# RATT_REV1.net
KiCad netlist of a schematic drawn in EAGLE
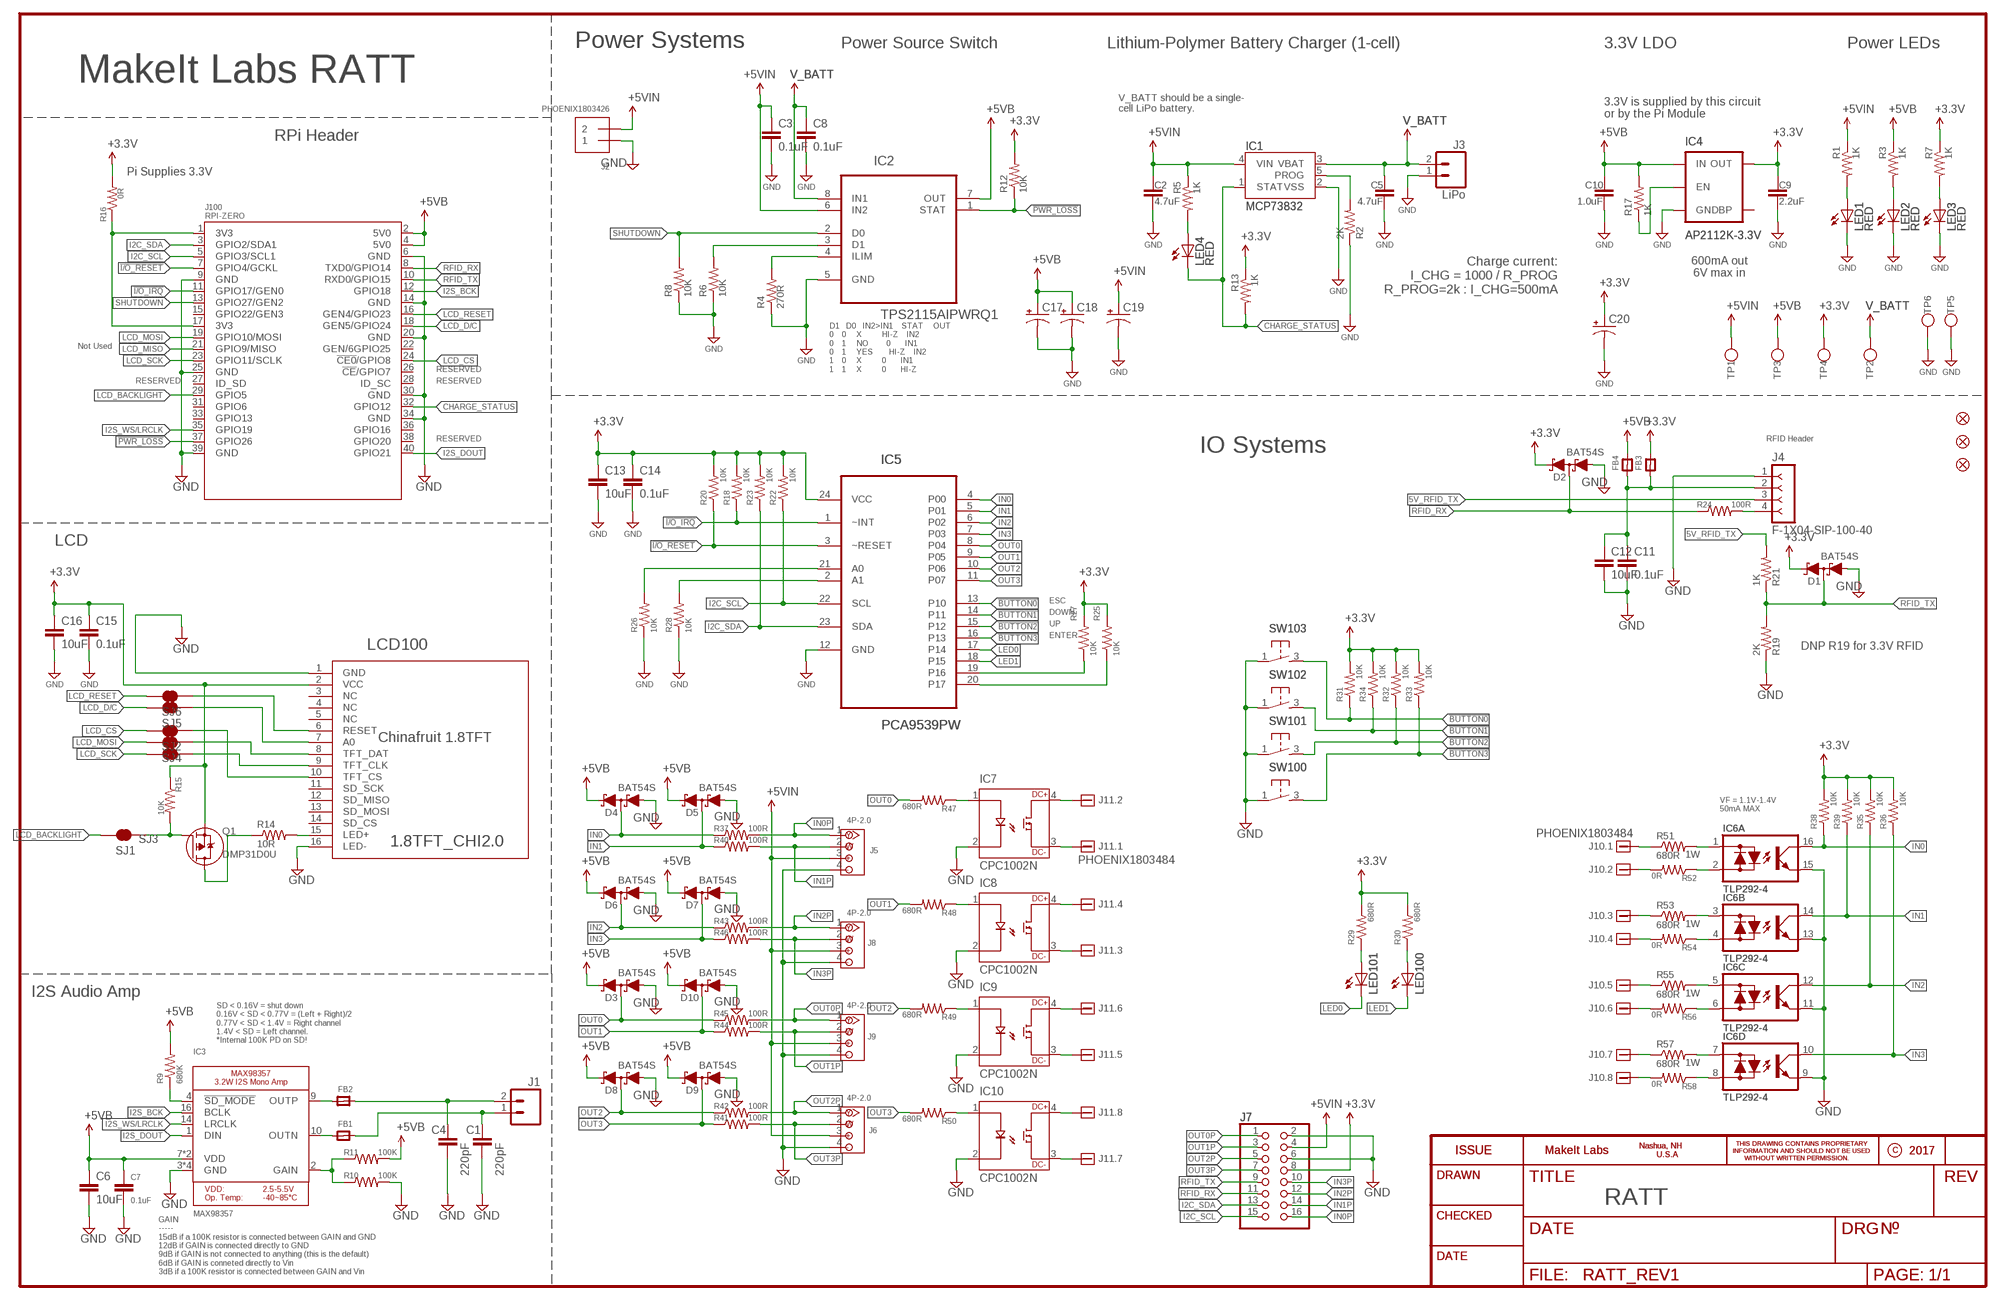
[diagram p0: schematic, sheet 1]

(export (version "E")
  (design (tool "Eeschema 10.0.6"))
  (components
    (comp (ref "C1")
      (value "220pF")
      (footprint "eagle-import:0603-CAP")
      (libsource (lib "eagle-import") (part "CAP0603"))
    )
    (comp (ref "C2")
      (value "4.7uF")
      (footprint "eagle-import:0603-CAP")
      (libsource (lib "eagle-import") (part "CAP0603"))
    )
    (comp (ref "C3")
      (value "0.1uF")
      (footprint "eagle-import:0603-CAP")
      (libsource (lib "eagle-import") (part "CAP0603"))
    )
    (comp (ref "C4")
      (value "220pF")
      (footprint "eagle-import:0603-CAP")
      (libsource (lib "eagle-import") (part "CAP0603"))
    )
    (comp (ref "C5")
      (value "4.7uF")
      (footprint "eagle-import:0603-CAP")
      (libsource (lib "eagle-import") (part "CAP0603"))
    )
    (comp (ref "C6")
      (value "10uF")
      (footprint "eagle-import:0805-CAP")
      (libsource (lib "eagle-import") (part "CAP0805"))
    )
    (comp (ref "C7")
      (value "0.1uF")
      (footprint "eagle-import:0603-CAP")
      (libsource (lib "eagle-import") (part "CAP0603"))
    )
    (comp (ref "C8")
      (value "0.1uF")
      (footprint "eagle-import:0603-CAP")
      (libsource (lib "eagle-import") (part "CAP0603"))
    )
    (comp (ref "C9")
      (value "2.2uF")
      (footprint "eagle-import:0603-CAP")
      (libsource (lib "eagle-import") (part "CAP0603"))
    )
    (comp (ref "C10")
      (value "1.0uF")
      (footprint "eagle-import:0603-CAP")
      (libsource (lib "eagle-import") (part "CAP0603"))
    )
    (comp (ref "C11")
      (value "0.1uF")
      (footprint "eagle-import:0603-CAP")
      (libsource (lib "eagle-import") (part "CAP0603"))
    )
    (comp (ref "C12")
      (value "10uF")
      (footprint "eagle-import:0805-CAP")
      (libsource (lib "eagle-import") (part "CAP0805"))
    )
    (comp (ref "C13")
      (value "10uF")
      (footprint "eagle-import:0805-CAP")
      (libsource (lib "eagle-import") (part "CAP0805"))
    )
    (comp (ref "C14")
      (value "0.1uF")
      (footprint "eagle-import:0603-CAP")
      (libsource (lib "eagle-import") (part "CAP0603"))
    )
    (comp (ref "C15")
      (value "0.1uF")
      (footprint "eagle-import:0603-CAP")
      (libsource (lib "eagle-import") (part "CAP0603"))
    )
    (comp (ref "C16")
      (value "10uF")
      (footprint "eagle-import:0805-CAP")
      (libsource (lib "eagle-import") (part "CAP0805"))
    )
    (comp (ref "C17")
      (value "CPOL-USD")
      (footprint "eagle-import:PANASONIC_D")
      (libsource (lib "eagle-import") (part "CPOL-USD"))
    )
    (comp (ref "C18")
      (value "CPOL-USD")
      (footprint "eagle-import:PANASONIC_D")
      (libsource (lib "eagle-import") (part "CPOL-USD"))
    )
    (comp (ref "C19")
      (value "CPOL-USD")
      (footprint "eagle-import:PANASONIC_D")
      (libsource (lib "eagle-import") (part "CPOL-USD"))
    )
    (comp (ref "C20")
      (value "CPOL-USD")
      (footprint "eagle-import:PANASONIC_D")
      (libsource (lib "eagle-import") (part "CPOL-USD"))
    )
    (comp (ref "D1")
      (value "BAT54S")
      (footprint "eagle-import:SOT-23")
      (libsource (lib "eagle-import") (part "BAT54S"))
    )
    (comp (ref "D2")
      (value "BAT54S")
      (footprint "eagle-import:SOT-23")
      (libsource (lib "eagle-import") (part "BAT54S"))
    )
    (comp (ref "D3")
      (value "BAT54S")
      (footprint "eagle-import:SOT-23")
      (libsource (lib "eagle-import") (part "BAT54S"))
    )
    (comp (ref "D4")
      (value "BAT54S")
      (footprint "eagle-import:SOT-23")
      (libsource (lib "eagle-import") (part "BAT54S"))
    )
    (comp (ref "D5")
      (value "BAT54S")
      (footprint "eagle-import:SOT-23")
      (libsource (lib "eagle-import") (part "BAT54S"))
    )
    (comp (ref "D6")
      (value "BAT54S")
      (footprint "eagle-import:SOT-23")
      (libsource (lib "eagle-import") (part "BAT54S"))
    )
    (comp (ref "D7")
      (value "BAT54S")
      (footprint "eagle-import:SOT-23")
      (libsource (lib "eagle-import") (part "BAT54S"))
    )
    (comp (ref "D8")
      (value "BAT54S")
      (footprint "eagle-import:SOT-23")
      (libsource (lib "eagle-import") (part "BAT54S"))
    )
    (comp (ref "D9")
      (value "BAT54S")
      (footprint "eagle-import:SOT-23")
      (libsource (lib "eagle-import") (part "BAT54S"))
    )
    (comp (ref "D10")
      (value "BAT54S")
      (footprint "eagle-import:SOT-23")
      (libsource (lib "eagle-import") (part "BAT54S"))
    )
    (comp (ref "FB1")
      (value "FERRITE")
      (footprint "eagle-import:0603")
      (libsource (lib "eagle-import") (part "FERRITE"))
    )
    (comp (ref "FB2")
      (value "FERRITE")
      (footprint "eagle-import:0603")
      (libsource (lib "eagle-import") (part "FERRITE"))
    )
    (comp (ref "FB3")
      (value "FERRITE")
      (footprint "eagle-import:0603")
      (libsource (lib "eagle-import") (part "FERRITE"))
    )
    (comp (ref "FB4")
      (value "FERRITE")
      (footprint "eagle-import:0603")
      (libsource (lib "eagle-import") (part "FERRITE"))
    )
    (comp (ref "FID1")
      (value "FIDUCIAL40MILX80MIL")
      (footprint "eagle-import:FIDUCIAL-40MILX80MIL")
      (libsource (lib "eagle-import") (part "FIDUCIAL40MILX80MIL"))
    )
    (comp (ref "FID2")
      (value "FIDUCIAL40MILX80MIL")
      (footprint "eagle-import:FIDUCIAL-40MILX80MIL")
      (libsource (lib "eagle-import") (part "FIDUCIAL40MILX80MIL"))
    )
    (comp (ref "FID3")
      (value "FIDUCIAL40MILX80MIL")
      (footprint "eagle-import:FIDUCIAL-40MILX80MIL")
      (libsource (lib "eagle-import") (part "FIDUCIAL40MILX80MIL"))
    )
    (comp (ref "IC1")
      (value "MCP73832")
      (footprint "eagle-import:SOT23-5")
      (libsource (lib "eagle-import") (part "MCP73831"))
    )
    (comp (ref "IC2")
      (value "TPS2115AIPWRQ1")
      (footprint "eagle-import:SOP65P640X120-8N")
      (libsource (lib "eagle-import") (part "TPS2115AIPWRQ1"))
    )
    (comp (ref "IC3")
      (value "MAX98357")
      (footprint "eagle-import:QFN16_3MM")
      (libsource (lib "eagle-import") (part "AUDIOAMP_MAX98357"))
    )
    (comp (ref "IC4")
      (value "AP2112K-3.3V")
      (footprint "eagle-import:SOT23-5")
      (libsource (lib "eagle-import") (part "V_REG_LDOSMD"))
    )
    (comp (ref "IC5")
      (value "PCA9539PW")
      (footprint "eagle-import:SOP65P640X120-24N")
      (libsource (lib "eagle-import") (part "PCA9539PW"))
    )
    (comp (ref "IC6")
      (value "TLP292-4")
      (footprint "eagle-import:SO-16")
      (libsource (lib "eagle-import") (part "TLP292-4"))
    )
    (comp (ref "IC7")
      (value "CPC1002N")
      (footprint "eagle-import:CPC1002N")
      (libsource (lib "eagle-import") (part "CPC1002N"))
    )
    (comp (ref "IC8")
      (value "CPC1002N")
      (footprint "eagle-import:CPC1002N")
      (libsource (lib "eagle-import") (part "CPC1002N"))
    )
    (comp (ref "IC9")
      (value "CPC1002N")
      (footprint "eagle-import:CPC1002N")
      (libsource (lib "eagle-import") (part "CPC1002N"))
    )
    (comp (ref "IC10")
      (value "CPC1002N")
      (footprint "eagle-import:CPC1002N")
      (libsource (lib "eagle-import") (part "CPC1002N"))
    )
    (comp (ref "J1")
      (value "M02POLAR")
      (footprint "eagle-import:MOLEX-1X2")
      (libsource (lib "eagle-import") (part "M02POLAR"))
    )
    (comp (ref "J2")
      (value "PHOENIX1803426")
      (footprint "eagle-import:1803426")
      (libsource (lib "eagle-import") (part "PHOENIX1803426"))
    )
    (comp (ref "J3")
      (value "LiPo")
      (footprint "eagle-import:JST-2-PTH")
      (libsource (lib "eagle-import") (part "M02JST-PTH-2"))
    )
    (comp (ref "J4")
      (value "F-1X04-SIP-100-40")
      (footprint "eagle-import:SIP-100-04-40")
      (libsource (lib "eagle-import") (part "F-1X04-SIP-100-40"))
    )
    (comp (ref "J5")
      (value "4P-2.0")
      (footprint "eagle-import:HW4-2.0")
      (libsource (lib "eagle-import") (part "GROVE-CONNECTOR-TH-VERT"))
    )
    (comp (ref "J6")
      (value "4P-2.0")
      (footprint "eagle-import:HW4-2.0")
      (libsource (lib "eagle-import") (part "GROVE-CONNECTOR-TH-VERT"))
    )
    (comp (ref "J7")
      (value "PINHD-2X8SHROUD")
      (footprint "eagle-import:2X08_SHROUD")
      (libsource (lib "eagle-import") (part "PINHD-2X8SHROUD"))
    )
    (comp (ref "J8")
      (value "4P-2.0")
      (footprint "eagle-import:HW4-2.0")
      (libsource (lib "eagle-import") (part "GROVE-CONNECTOR-TH-VERT"))
    )
    (comp (ref "J9")
      (value "4P-2.0")
      (footprint "eagle-import:HW4-2.0")
      (libsource (lib "eagle-import") (part "GROVE-CONNECTOR-TH-VERT"))
    )
    (comp (ref "J10")
      (value "PHOENIX1803484")
      (footprint "eagle-import:1803484")
      (libsource (lib "eagle-import") (part "PHOENIX1803484"))
    )
    (comp (ref "J11")
      (value "PHOENIX1803484")
      (footprint "eagle-import:1803484")
      (libsource (lib "eagle-import") (part "PHOENIX1803484"))
    )
    (comp (ref "J100")
      (value "RPI-ZERO")
      (footprint "eagle-import:RASPBERRYPI_BASTELSTUBE_V13_RASPI_BOARD_B+_FULL")
      (libsource (lib "eagle-import") (part "RPI-ZERO"))
    )
    (comp (ref "LCD100")
      (value "1.8TFT_CHI2.0")
      (footprint "eagle-import:1.8TFT_CHI_2.0")
      (libsource (lib "eagle-import") (part "1.8TFT_CHI2.0"))
    )
    (comp (ref "LED1")
      (value "RED")
      (footprint "eagle-import:LED-0603")
      (libsource (lib "eagle-import") (part "LED-RED0603"))
    )
    (comp (ref "LED2")
      (value "RED")
      (footprint "eagle-import:LED-0603")
      (libsource (lib "eagle-import") (part "LED-RED0603"))
    )
    (comp (ref "LED3")
      (value "RED")
      (footprint "eagle-import:LED-0603")
      (libsource (lib "eagle-import") (part "LED-RED0603"))
    )
    (comp (ref "LED4")
      (value "RED")
      (footprint "eagle-import:LED-0603")
      (libsource (lib "eagle-import") (part "LED-RED0603"))
    )
    (comp (ref "LED100")
      (value "LED5MM")
      (footprint "eagle-import:LED5MM")
      (libsource (lib "eagle-import") (part "LED5MM"))
    )
    (comp (ref "LED101")
      (value "LED5MM")
      (footprint "eagle-import:LED5MM")
      (libsource (lib "eagle-import") (part "LED5MM"))
    )
    (comp (ref "Q1")
      (value "DMP31D0U")
      (footprint "eagle-import:SOT23")
      (libsource (lib "eagle-import") (part "DMP31D0U"))
    )
    (comp (ref "R1")
      (value "1K")
      (footprint "eagle-import:0603-RES")
      (libsource (lib "eagle-import") (part "RESISTOR0603"))
    )
    (comp (ref "R2")
      (value "2K")
      (footprint "eagle-import:0603-RES")
      (libsource (lib "eagle-import") (part "RESISTOR0603"))
    )
    (comp (ref "R3")
      (value "1K")
      (footprint "eagle-import:0603-RES")
      (libsource (lib "eagle-import") (part "RESISTOR0603"))
    )
    (comp (ref "R4")
      (value "270R")
      (footprint "eagle-import:0603-RES")
      (libsource (lib "eagle-import") (part "RESISTOR0603"))
    )
    (comp (ref "R5")
      (value "1K")
      (footprint "eagle-import:0603-RES")
      (libsource (lib "eagle-import") (part "RESISTOR0603"))
    )
    (comp (ref "R6")
      (value "10K")
      (footprint "eagle-import:0603-RES")
      (libsource (lib "eagle-import") (part "RESISTOR0603"))
    )
    (comp (ref "R7")
      (value "1K")
      (footprint "eagle-import:0603-RES")
      (libsource (lib "eagle-import") (part "RESISTOR0603"))
    )
    (comp (ref "R8")
      (value "10K")
      (footprint "eagle-import:0603-RES")
      (libsource (lib "eagle-import") (part "RESISTOR0603"))
    )
    (comp (ref "R9")
      (value "680K")
      (footprint "eagle-import:0603-RES")
      (libsource (lib "eagle-import") (part "RESISTOR0603"))
    )
    (comp (ref "R10")
      (value "100K")
      (footprint "eagle-import:0603-RES")
      (libsource (lib "eagle-import") (part "RESISTOR0603"))
    )
    (comp (ref "R11")
      (value "100K")
      (footprint "eagle-import:0603-RES")
      (libsource (lib "eagle-import") (part "RESISTOR0603"))
    )
    (comp (ref "R12")
      (value "10K")
      (footprint "eagle-import:0603-RES")
      (libsource (lib "eagle-import") (part "RESISTOR0603"))
    )
    (comp (ref "R13")
      (value "1K")
      (footprint "eagle-import:0603-RES")
      (libsource (lib "eagle-import") (part "RESISTOR0603"))
    )
    (comp (ref "R14")
      (value "10R")
      (footprint "eagle-import:1206-RES")
      (libsource (lib "eagle-import") (part "RESISTOR1206"))
    )
    (comp (ref "R15")
      (value "10K")
      (footprint "eagle-import:0603-RES")
      (libsource (lib "eagle-import") (part "RESISTOR0603"))
    )
    (comp (ref "R16")
      (value "0R")
      (footprint "eagle-import:0603-RES")
      (libsource (lib "eagle-import") (part "RESISTOR0603"))
    )
    (comp (ref "R17")
      (value "1K")
      (footprint "eagle-import:0603-RES")
      (libsource (lib "eagle-import") (part "RESISTOR0603"))
    )
    (comp (ref "R18")
      (value "10K")
      (footprint "eagle-import:0603-RES")
      (libsource (lib "eagle-import") (part "RESISTOR0603"))
    )
    (comp (ref "R19")
      (value "2K")
      (footprint "eagle-import:0603-RES")
      (libsource (lib "eagle-import") (part "RESISTOR0603"))
    )
    (comp (ref "R20")
      (value "10K")
      (footprint "eagle-import:0603-RES")
      (libsource (lib "eagle-import") (part "RESISTOR0603"))
    )
    (comp (ref "R21")
      (value "1K")
      (footprint "eagle-import:0603-RES")
      (libsource (lib "eagle-import") (part "RESISTOR0603"))
    )
    (comp (ref "R22")
      (value "10K")
      (footprint "eagle-import:0603-RES")
      (libsource (lib "eagle-import") (part "RESISTOR0603"))
    )
    (comp (ref "R23")
      (value "10K")
      (footprint "eagle-import:0603-RES")
      (libsource (lib "eagle-import") (part "RESISTOR0603"))
    )
    (comp (ref "R24")
      (value "100R")
      (footprint "eagle-import:0603-RES")
      (libsource (lib "eagle-import") (part "RESISTOR0603"))
    )
    (comp (ref "R25")
      (value "10K")
      (footprint "eagle-import:0603-RES")
      (libsource (lib "eagle-import") (part "RESISTOR0603"))
    )
    (comp (ref "R26")
      (value "10K")
      (footprint "eagle-import:0603-RES")
      (libsource (lib "eagle-import") (part "RESISTOR0603"))
    )
    (comp (ref "R27")
      (value "10K")
      (footprint "eagle-import:0603-RES")
      (libsource (lib "eagle-import") (part "RESISTOR0603"))
    )
    (comp (ref "R28")
      (value "10K")
      (footprint "eagle-import:0603-RES")
      (libsource (lib "eagle-import") (part "RESISTOR0603"))
    )
    (comp (ref "R29")
      (value "680R")
      (footprint "eagle-import:0603-RES")
      (libsource (lib "eagle-import") (part "RESISTOR0603"))
    )
    (comp (ref "R30")
      (value "680R")
      (footprint "eagle-import:0603-RES")
      (libsource (lib "eagle-import") (part "RESISTOR0603"))
    )
    (comp (ref "R31")
      (value "10K")
      (footprint "eagle-import:0603-RES")
      (libsource (lib "eagle-import") (part "RESISTOR0603"))
    )
    (comp (ref "R32")
      (value "10K")
      (footprint "eagle-import:0603-RES")
      (libsource (lib "eagle-import") (part "RESISTOR0603"))
    )
    (comp (ref "R33")
      (value "10K")
      (footprint "eagle-import:0603-RES")
      (libsource (lib "eagle-import") (part "RESISTOR0603"))
    )
    (comp (ref "R34")
      (value "10K")
      (footprint "eagle-import:0603-RES")
      (libsource (lib "eagle-import") (part "RESISTOR0603"))
    )
    (comp (ref "R35")
      (value "10K")
      (footprint "eagle-import:0603-RES")
      (libsource (lib "eagle-import") (part "RESISTOR0603"))
    )
    (comp (ref "R36")
      (value "10K")
      (footprint "eagle-import:0603-RES")
      (libsource (lib "eagle-import") (part "RESISTOR0603"))
    )
    (comp (ref "R37")
      (value "100R")
      (footprint "eagle-import:0603-RES")
      (libsource (lib "eagle-import") (part "RESISTOR0603"))
    )
    (comp (ref "R38")
      (value "10K")
      (footprint "eagle-import:0603-RES")
      (libsource (lib "eagle-import") (part "RESISTOR0603"))
    )
    (comp (ref "R39")
      (value "10K")
      (footprint "eagle-import:0603-RES")
      (libsource (lib "eagle-import") (part "RESISTOR0603"))
    )
    (comp (ref "R40")
      (value "100R")
      (footprint "eagle-import:0603-RES")
      (libsource (lib "eagle-import") (part "RESISTOR0603"))
    )
    (comp (ref "R41")
      (value "100R")
      (footprint "eagle-import:0603-RES")
      (libsource (lib "eagle-import") (part "RESISTOR0603"))
    )
    (comp (ref "R42")
      (value "100R")
      (footprint "eagle-import:0603-RES")
      (libsource (lib "eagle-import") (part "RESISTOR0603"))
    )
    (comp (ref "R43")
      (value "100R")
      (footprint "eagle-import:0603-RES")
      (libsource (lib "eagle-import") (part "RESISTOR0603"))
    )
    (comp (ref "R44")
      (value "100R")
      (footprint "eagle-import:0603-RES")
      (libsource (lib "eagle-import") (part "RESISTOR0603"))
    )
    (comp (ref "R45")
      (value "100R")
      (footprint "eagle-import:0603-RES")
      (libsource (lib "eagle-import") (part "RESISTOR0603"))
    )
    (comp (ref "R46")
      (value "100R")
      (footprint "eagle-import:0603-RES")
      (libsource (lib "eagle-import") (part "RESISTOR0603"))
    )
    (comp (ref "R47")
      (value "680R")
      (footprint "eagle-import:0603-RES")
      (libsource (lib "eagle-import") (part "RESISTOR0603"))
    )
    (comp (ref "R48")
      (value "680R")
      (footprint "eagle-import:0603-RES")
      (libsource (lib "eagle-import") (part "RESISTOR0603"))
    )
    (comp (ref "R49")
      (value "680R")
      (footprint "eagle-import:0603-RES")
      (libsource (lib "eagle-import") (part "RESISTOR0603"))
    )
    (comp (ref "R50")
      (value "680R")
      (footprint "eagle-import:0603-RES")
      (libsource (lib "eagle-import") (part "RESISTOR0603"))
    )
    (comp (ref "R51")
      (value "680R")
      (footprint "eagle-import:2512-RES")
      (fields (field (name "P") "1W"))
      (libsource (lib "eagle-import") (part "RESISTOR2512"))
    )
    (comp (ref "R52")
      (value "0R")
      (footprint "eagle-import:0603-RES")
      (libsource (lib "eagle-import") (part "RESISTOR0603"))
    )
    (comp (ref "R53")
      (value "680R")
      (footprint "eagle-import:2512-RES")
      (fields (field (name "P") "1W"))
      (libsource (lib "eagle-import") (part "RESISTOR2512"))
    )
    (comp (ref "R54")
      (value "0R")
      (footprint "eagle-import:0603-RES")
      (libsource (lib "eagle-import") (part "RESISTOR0603"))
    )
    (comp (ref "R55")
      (value "680R")
      (footprint "eagle-import:2512-RES")
      (fields (field (name "P") "1W"))
      (libsource (lib "eagle-import") (part "RESISTOR2512"))
    )
    (comp (ref "R56")
      (value "0R")
      (footprint "eagle-import:0603-RES")
      (libsource (lib "eagle-import") (part "RESISTOR0603"))
    )
    (comp (ref "R57")
      (value "680R")
      (footprint "eagle-import:2512-RES")
      (fields (field (name "P") "1W"))
      (libsource (lib "eagle-import") (part "RESISTOR2512"))
    )
    (comp (ref "R58")
      (value "0R")
      (footprint "eagle-import:0603-RES")
      (libsource (lib "eagle-import") (part "RESISTOR0603"))
    )
    (comp (ref "SJ1")
      (value "JUMPER-PAD-2-NC_BY_TRACE")
      (footprint "eagle-import:SOLDERJUMPER_10MIL")
      (libsource (lib "eagle-import") (part "SOLDERJUMPER_CLOSED10MIL"))
    )
    (comp (ref "SJ2")
      (value "JUMPER-PAD-2-NC_BY_TRACE")
      (footprint "eagle-import:SOLDERJUMPER_10MIL")
      (libsource (lib "eagle-import") (part "SOLDERJUMPER_CLOSED10MIL"))
    )
    (comp (ref "SJ3")
      (value "JUMPER-PAD-2-NC_BY_TRACE")
      (footprint "eagle-import:SOLDERJUMPER_10MIL")
      (libsource (lib "eagle-import") (part "SOLDERJUMPER_CLOSED10MIL"))
    )
    (comp (ref "SJ4")
      (value "JUMPER-PAD-2-NC_BY_TRACE")
      (footprint "eagle-import:SOLDERJUMPER_10MIL")
      (libsource (lib "eagle-import") (part "SOLDERJUMPER_CLOSED10MIL"))
    )
    (comp (ref "SJ5")
      (value "JUMPER-PAD-2-NC_BY_TRACE")
      (footprint "eagle-import:SOLDERJUMPER_10MIL")
      (libsource (lib "eagle-import") (part "SOLDERJUMPER_CLOSED10MIL"))
    )
    (comp (ref "SJ6")
      (value "JUMPER-PAD-2-NC_BY_TRACE")
      (footprint "eagle-import:SOLDERJUMPER_10MIL")
      (libsource (lib "eagle-import") (part "SOLDERJUMPER_CLOSED10MIL"))
    )
    (comp (ref "SW100")
      (value "ESWITCH_320")
      (footprint "eagle-import:ESWITCH320")
      (libsource (lib "eagle-import") (part "ESWITCH_320"))
    )
    (comp (ref "SW101")
      (value "ESWITCH_320")
      (footprint "eagle-import:ESWITCH320")
      (libsource (lib "eagle-import") (part "ESWITCH_320"))
    )
    (comp (ref "SW102")
      (value "ESWITCH_320")
      (footprint "eagle-import:ESWITCH320")
      (libsource (lib "eagle-import") (part "ESWITCH_320"))
    )
    (comp (ref "SW103")
      (value "ESWITCH_320")
      (footprint "eagle-import:ESWITCH320")
      (libsource (lib "eagle-import") (part "ESWITCH_320"))
    )
    (comp (ref "TP1")
      (value "5VIN")
      (footprint "eagle-import:1206-RCW")
      (libsource (lib "eagle-import") (part "RCW-0C"))
    )
    (comp (ref "TP2")
      (value "BATT")
      (footprint "eagle-import:1206-RCW")
      (libsource (lib "eagle-import") (part "RCW-0C"))
    )
    (comp (ref "TP3")
      (value "5VB")
      (footprint "eagle-import:1206-RCW")
      (libsource (lib "eagle-import") (part "RCW-0C"))
    )
    (comp (ref "TP4")
      (value "3.3V")
      (footprint "eagle-import:1206-RCW")
      (libsource (lib "eagle-import") (part "RCW-0C"))
    )
    (comp (ref "TP5")
      (value "GND")
      (footprint "eagle-import:1206-RCW")
      (libsource (lib "eagle-import") (part "RCW-0C"))
    )
    (comp (ref "TP6")
      (value "GND")
      (footprint "eagle-import:1206-RCW")
      (libsource (lib "eagle-import") (part "RCW-0C"))
    )
  )
  (nets
    (net (code "1") (name "+3.3V") (class "Default")
      (node (ref "C13") (pin "1") (pinfunction "1_1") (pintype "passive"))
      (node (ref "C14") (pin "1") (pinfunction "1_1") (pintype "passive"))
      (node (ref "C15") (pin "1") (pinfunction "1_1") (pintype "passive"))
      (node (ref "C16") (pin "1") (pinfunction "1_1") (pintype "passive"))
      (node (ref "C20") (pin "+") (pinfunction "+_+") (pintype "passive"))
      (node (ref "C9") (pin "1") (pinfunction "1_1") (pintype "passive"))
      (node (ref "D1") (pin "2") (pinfunction "C2_2") (pintype "passive"))
      (node (ref "D2") (pin "2") (pinfunction "C2_2") (pintype "passive"))
      (node (ref "FB3") (pin "2") (pinfunction "P$2_2") (pintype "passive"))
      (node (ref "IC4") (pin "5") (pinfunction "OUT_5") (pintype "passive"))
      (node (ref "IC5") (pin "24") (pinfunction "VCC_24") (pintype "power_in"))
      (node (ref "J7") (pin "8") (pinfunction "8_8") (pintype "passive"))
      (node (ref "LCD100") (pin "2") (pinfunction "VCC_2") (pintype "bidirectional"))
      (node (ref "Q1") (pin "2") (pinfunction "S_2") (pintype "passive"))
      (node (ref "R12") (pin "2") (pinfunction "2_2") (pintype "passive"))
      (node (ref "R13") (pin "1") (pinfunction "1_1") (pintype "passive"))
      (node (ref "R15") (pin "1") (pinfunction "1_1") (pintype "passive"))
      (node (ref "R16") (pin "2") (pinfunction "2_2") (pintype "passive"))
      (node (ref "R18") (pin "2") (pinfunction "2_2") (pintype "passive"))
      (node (ref "R20") (pin "2") (pinfunction "2_2") (pintype "passive"))
      (node (ref "R22") (pin "2") (pinfunction "2_2") (pintype "passive"))
      (node (ref "R23") (pin "2") (pinfunction "2_2") (pintype "passive"))
      (node (ref "R25") (pin "2") (pinfunction "2_2") (pintype "passive"))
      (node (ref "R27") (pin "2") (pinfunction "2_2") (pintype "passive"))
      (node (ref "R29") (pin "2") (pinfunction "2_2") (pintype "passive"))
      (node (ref "R30") (pin "2") (pinfunction "2_2") (pintype "passive"))
      (node (ref "R31") (pin "2") (pinfunction "2_2") (pintype "passive"))
      (node (ref "R32") (pin "2") (pinfunction "2_2") (pintype "passive"))
      (node (ref "R33") (pin "2") (pinfunction "2_2") (pintype "passive"))
      (node (ref "R34") (pin "2") (pinfunction "2_2") (pintype "passive"))
      (node (ref "R35") (pin "2") (pinfunction "2_2") (pintype "passive"))
      (node (ref "R36") (pin "2") (pinfunction "2_2") (pintype "passive"))
      (node (ref "R38") (pin "2") (pinfunction "2_2") (pintype "passive"))
      (node (ref "R39") (pin "2") (pinfunction "2_2") (pintype "passive"))
      (node (ref "R7") (pin "1") (pinfunction "1_1") (pintype "passive"))
      (node (ref "TP4") (pin "1") (pinfunction "TP_1") (pintype "bidirectional"))
    )
    (net (code "2") (name "+5VB") (class "Default")
      (node (ref "C10") (pin "1") (pinfunction "1_1") (pintype "passive"))
      (node (ref "C17") (pin "+") (pinfunction "+_+") (pintype "passive"))
      (node (ref "C18") (pin "+") (pinfunction "+_+") (pintype "passive"))
      (node (ref "C6") (pin "1") (pinfunction "1_1") (pintype "passive"))
      (node (ref "C7") (pin "1") (pinfunction "1_1") (pintype "passive"))
      (node (ref "D10") (pin "2") (pinfunction "C2_2") (pintype "passive"))
      (node (ref "D3") (pin "2") (pinfunction "C2_2") (pintype "passive"))
      (node (ref "D4") (pin "2") (pinfunction "C2_2") (pintype "passive"))
      (node (ref "D5") (pin "2") (pinfunction "C2_2") (pintype "passive"))
      (node (ref "D6") (pin "2") (pinfunction "C2_2") (pintype "passive"))
      (node (ref "D7") (pin "2") (pinfunction "C2_2") (pintype "passive"))
      (node (ref "D8") (pin "2") (pinfunction "C2_2") (pintype "passive"))
      (node (ref "D9") (pin "2") (pinfunction "C2_2") (pintype "passive"))
      (node (ref "FB4") (pin "2") (pinfunction "P$2_2") (pintype "passive"))
      (node (ref "IC2") (pin "7") (pinfunction "OUT_7") (pintype "output"))
      (node (ref "IC3") (pin "7") (pinfunction "VDD_7") (pintype "power_in"))
      (node (ref "IC3") (pin "8") (pinfunction "VDD_8") (pintype "power_in"))
      (node (ref "IC4") (pin "1") (pinfunction "IN_1") (pintype "input"))
      (node (ref "J100") (pin "2") (pinfunction "5V0_2") (pintype "power_in"))
      (node (ref "J100") (pin "4") (pinfunction "5V0_4") (pintype "power_in"))
      (node (ref "R11") (pin "2") (pinfunction "2_2") (pintype "passive"))
      (node (ref "R17") (pin "2") (pinfunction "2_2") (pintype "passive"))
      (node (ref "R3") (pin "1") (pinfunction "1_1") (pintype "passive"))
      (node (ref "R9") (pin "2") (pinfunction "2_2") (pintype "passive"))
      (node (ref "TP3") (pin "1") (pinfunction "TP_1") (pintype "bidirectional"))
    )
    (net (code "3") (name "+5VIN") (class "Default")
      (node (ref "C19") (pin "+") (pinfunction "+_+") (pintype "passive"))
      (node (ref "C2") (pin "1") (pinfunction "1_1") (pintype "passive"))
      (node (ref "C3") (pin "1") (pinfunction "1_1") (pintype "passive"))
      (node (ref "IC1") (pin "4") (pinfunction "VIN_4") (pintype "power_in"))
      (node (ref "IC2") (pin "6") (pinfunction "IN2_6") (pintype "power_in"))
      (node (ref "J2") (pin "2") (pinfunction "2_2") (pintype "passive"))
      (node (ref "J5") (pin "3") (pinfunction "3_3") (pintype "bidirectional"))
      (node (ref "J6") (pin "3") (pinfunction "3_3") (pintype "bidirectional"))
      (node (ref "J7") (pin "4") (pinfunction "4_4") (pintype "passive"))
      (node (ref "J8") (pin "3") (pinfunction "3_3") (pintype "bidirectional"))
      (node (ref "J9") (pin "3") (pinfunction "3_3") (pintype "bidirectional"))
      (node (ref "R1") (pin "1") (pinfunction "1_1") (pintype "passive"))
      (node (ref "R5") (pin "1") (pinfunction "1_1") (pintype "passive"))
      (node (ref "TP1") (pin "1") (pinfunction "TP_1") (pintype "bidirectional"))
    )
    (net (code "4") (name "/GND") (class "Default")
      (node (ref "C1") (pin "2") (pinfunction "2_2") (pintype "passive"))
      (node (ref "C10") (pin "2") (pinfunction "2_2") (pintype "passive"))
      (node (ref "C11") (pin "2") (pinfunction "2_2") (pintype "passive"))
      (node (ref "C12") (pin "2") (pinfunction "2_2") (pintype "passive"))
      (node (ref "C13") (pin "2") (pinfunction "2_2") (pintype "passive"))
      (node (ref "C14") (pin "2") (pinfunction "2_2") (pintype "passive"))
      (node (ref "C15") (pin "2") (pinfunction "2_2") (pintype "passive"))
      (node (ref "C16") (pin "2") (pinfunction "2_2") (pintype "passive"))
      (node (ref "C17") (pin "-") (pinfunction "-_-") (pintype "passive"))
      (node (ref "C18") (pin "-") (pinfunction "-_-") (pintype "passive"))
      (node (ref "C19") (pin "-") (pinfunction "-_-") (pintype "passive"))
      (node (ref "C2") (pin "2") (pinfunction "2_2") (pintype "passive"))
      (node (ref "C20") (pin "-") (pinfunction "-_-") (pintype "passive"))
      (node (ref "C3") (pin "2") (pinfunction "2_2") (pintype "passive"))
      (node (ref "C4") (pin "2") (pinfunction "2_2") (pintype "passive"))
      (node (ref "C5") (pin "2") (pinfunction "2_2") (pintype "passive"))
      (node (ref "C6") (pin "2") (pinfunction "2_2") (pintype "passive"))
      (node (ref "C7") (pin "2") (pinfunction "2_2") (pintype "passive"))
      (node (ref "C8") (pin "2") (pinfunction "2_2") (pintype "passive"))
      (node (ref "C9") (pin "2") (pinfunction "2_2") (pintype "passive"))
      (node (ref "D1") (pin "1") (pinfunction "A1_1") (pintype "passive"))
      (node (ref "D10") (pin "1") (pinfunction "A1_1") (pintype "passive"))
      (node (ref "D2") (pin "1") (pinfunction "A1_1") (pintype "passive"))
      (node (ref "D3") (pin "1") (pinfunction "A1_1") (pintype "passive"))
      (node (ref "D4") (pin "1") (pinfunction "A1_1") (pintype "passive"))
      (node (ref "D5") (pin "1") (pinfunction "A1_1") (pintype "passive"))
      (node (ref "D6") (pin "1") (pinfunction "A1_1") (pintype "passive"))
      (node (ref "D7") (pin "1") (pinfunction "A1_1") (pintype "passive"))
      (node (ref "D8") (pin "1") (pinfunction "A1_1") (pintype "passive"))
      (node (ref "D9") (pin "1") (pinfunction "A1_1") (pintype "passive"))
      (node (ref "IC1") (pin "2") (pinfunction "VSS_2") (pintype "power_in"))
      (node (ref "IC10") (pin "2") (pinfunction "CATHODE_2") (pintype "passive"))
      (node (ref "IC2") (pin "5") (pinfunction "GND_5") (pintype "passive"))
      (node (ref "IC3") (pin "11") (pinfunction "GND_11") (pintype "power_in"))
      (node (ref "IC3") (pin "15") (pinfunction "GND_15") (pintype "power_in"))
      (node (ref "IC3") (pin "3") (pinfunction "GND_3") (pintype "power_in"))
      (node (ref "IC3") (pin "THERMAL") (pinfunction "GND_THERMAL") (pintype "power_in"))
      (node (ref "IC4") (pin "2") (pinfunction "GND_2") (pintype "input"))
      (node (ref "IC5") (pin "12") (pinfunction "GND_12") (pintype "passive"))
      (node (ref "IC6") (pin "11") (pinfunction "E_11") (pintype "passive"))
      (node (ref "IC6") (pin "13") (pinfunction "E_13") (pintype "passive"))
      (node (ref "IC6") (pin "15") (pinfunction "E_15") (pintype "passive"))
      (node (ref "IC6") (pin "9") (pinfunction "E_9") (pintype "passive"))
      (node (ref "IC7") (pin "2") (pinfunction "CATHODE_2") (pintype "passive"))
      (node (ref "IC8") (pin "2") (pinfunction "CATHODE_2") (pintype "passive"))
      (node (ref "IC9") (pin "2") (pinfunction "CATHODE_2") (pintype "passive"))
      (node (ref "J100") (pin "14") (pinfunction "GND_14") (pintype "power_in"))
      (node (ref "J100") (pin "20") (pinfunction "GND_20") (pintype "power_in"))
      (node (ref "J100") (pin "25") (pinfunction "GND_25") (pintype "power_in"))
      (node (ref "J100") (pin "30") (pinfunction "GND_30") (pintype "power_in"))
      (node (ref "J100") (pin "34") (pinfunction "GND_34") (pintype "power_in"))
      (node (ref "J100") (pin "39") (pinfunction "GND_39") (pintype "power_in"))
      (node (ref "J100") (pin "6") (pinfunction "GND_6") (pintype "power_in"))
      (node (ref "J100") (pin "9") (pinfunction "GND_9") (pintype "power_in"))
      (node (ref "J2") (pin "1") (pinfunction "1_1") (pintype "passive"))
      (node (ref "J3") (pin "1") (pinfunction "1_1") (pintype "passive"))
      (node (ref "J4") (pin "1") (pinfunction "1_1") (pintype "passive"))
      (node (ref "J5") (pin "4") (pinfunction "4_4") (pintype "bidirectional"))
      (node (ref "J6") (pin "4") (pinfunction "4_4") (pintype "bidirectional"))
      (node (ref "J7") (pin "2") (pinfunction "2_2") (pintype "passive"))
      (node (ref "J7") (pin "6") (pinfunction "6_6") (pintype "passive"))
      (node (ref "J8") (pin "4") (pinfunction "4_4") (pintype "bidirectional"))
      (node (ref "J9") (pin "4") (pinfunction "4_4") (pintype "bidirectional"))
      (node (ref "LCD100") (pin "1") (pinfunction "GND_1") (pintype "bidirectional"))
      (node (ref "LCD100") (pin "16") (pinfunction "LED-_16") (pintype "bidirectional"))
      (node (ref "LED1") (pin "C") (pinfunction "C_C") (pintype "passive"))
      (node (ref "LED2") (pin "C") (pinfunction "C_C") (pintype "passive"))
      (node (ref "LED3") (pin "C") (pinfunction "C_C") (pintype "passive"))
      (node (ref "R10") (pin "2") (pinfunction "2_2") (pintype "passive"))
      (node (ref "R19") (pin "1") (pinfunction "1_1") (pintype "passive"))
      (node (ref "R2") (pin "1") (pinfunction "1_1") (pintype "passive"))
      (node (ref "R26") (pin "1") (pinfunction "1_1") (pintype "passive"))
      (node (ref "R28") (pin "1") (pinfunction "1_1") (pintype "passive"))
      (node (ref "R4") (pin "1") (pinfunction "1_1") (pintype "passive"))
      (node (ref "R6") (pin "1") (pinfunction "1_1") (pintype "passive"))
      (node (ref "R8") (pin "1") (pinfunction "1_1") (pintype "passive"))
      (node (ref "SW100") (pin "1") (pinfunction "1_1") (pintype "passive"))
      (node (ref "SW101") (pin "1") (pinfunction "1_1") (pintype "passive"))
      (node (ref "SW102") (pin "1") (pinfunction "1_1") (pintype "passive"))
      (node (ref "SW103") (pin "1") (pinfunction "1_1") (pintype "passive"))
      (node (ref "TP5") (pin "1") (pinfunction "TP_1") (pintype "bidirectional"))
      (node (ref "TP6") (pin "1") (pinfunction "TP_1") (pintype "bidirectional"))
    )
    (net (code "5") (name "/V_BATT") (class "Default")
      (node (ref "C5") (pin "1") (pinfunction "1_1") (pintype "passive"))
      (node (ref "C8") (pin "1") (pinfunction "1_1") (pintype "passive"))
      (node (ref "IC1") (pin "3") (pinfunction "VBAT_3") (pintype "power_in"))
      (node (ref "IC2") (pin "8") (pinfunction "IN1_8") (pintype "power_in"))
      (node (ref "J3") (pin "2") (pinfunction "2_2") (pintype "passive"))
      (node (ref "TP2") (pin "1") (pinfunction "TP_1") (pintype "bidirectional"))
    )
    (net (code "6") (name "/~{BUTTON0}") (class "Default")
      (node (ref "IC5") (pin "13") (pinfunction "P10_13") (pintype "bidirectional"))
      (node (ref "R31") (pin "1") (pinfunction "1_1") (pintype "passive"))
      (node (ref "SW103") (pin "3") (pinfunction "3_3") (pintype "passive"))
    )
    (net (code "7") (name "/~{BUTTON1}") (class "Default")
      (node (ref "IC5") (pin "14") (pinfunction "P11_14") (pintype "bidirectional"))
      (node (ref "R34") (pin "1") (pinfunction "1_1") (pintype "passive"))
      (node (ref "SW102") (pin "3") (pinfunction "3_3") (pintype "passive"))
    )
    (net (code "8") (name "/~{BUTTON2}") (class "Default")
      (node (ref "IC5") (pin "15") (pinfunction "P12_15") (pintype "bidirectional"))
      (node (ref "R32") (pin "1") (pinfunction "1_1") (pintype "passive"))
      (node (ref "SW101") (pin "3") (pinfunction "3_3") (pintype "passive"))
    )
    (net (code "9") (name "/~{BUTTON3}") (class "Default")
      (node (ref "IC5") (pin "16") (pinfunction "P13_16") (pintype "bidirectional"))
      (node (ref "R33") (pin "1") (pinfunction "1_1") (pintype "passive"))
      (node (ref "SW100") (pin "3") (pinfunction "3_3") (pintype "passive"))
    )
    (net (code "10") (name "/~{I{slash}O_IRQ}") (class "Default")
      (node (ref "IC5") (pin "1") (pinfunction "~{INT}_1") (pintype "output"))
      (node (ref "J100") (pin "11") (pinfunction "GPIO17/GEN0_11") (pintype "bidirectional"))
      (node (ref "R18") (pin "1") (pinfunction "1_1") (pintype "passive"))
    )
    (net (code "11") (name "/~{I{slash}O_RESET}") (class "Default")
      (node (ref "IC5") (pin "3") (pinfunction "~{RESET}_3") (pintype "input"))
      (node (ref "J100") (pin "7") (pinfunction "GPIO4/GCKL_7") (pintype "bidirectional"))
      (node (ref "R20") (pin "1") (pinfunction "1_1") (pintype "passive"))
    )
    (net (code "12") (name "/~{PWR_LOSS}") (class "Default")
      (node (ref "IC2") (pin "1") (pinfunction "STAT_1") (pintype "output"))
      (node (ref "J100") (pin "37") (pinfunction "GPIO26_37") (pintype "bidirectional"))
      (node (ref "R12") (pin "1") (pinfunction "1_1") (pintype "passive"))
    )
    (net (code "13") (name "5V_RFID_TX") (class "Default")
      (node (ref "J4") (pin "3") (pinfunction "3_3") (pintype "passive"))
      (node (ref "R21") (pin "2") (pinfunction "2_2") (pintype "passive"))
    )
    (net (code "14") (name "CHARGE_STATUS") (class "Default")
      (node (ref "IC1") (pin "1") (pinfunction "STAT_1") (pintype "output"))
      (node (ref "J100") (pin "32") (pinfunction "GPIO12_32") (pintype "bidirectional"))
      (node (ref "LED4") (pin "C") (pinfunction "C_C") (pintype "passive"))
      (node (ref "R13") (pin "2") (pinfunction "2_2") (pintype "passive"))
    )
    (net (code "15") (name "I2C_SCL") (class "Default")
      (node (ref "IC5") (pin "22") (pinfunction "SCL_22") (pintype "input"))
      (node (ref "J100") (pin "5") (pinfunction "GPIO3/SCL1_5") (pintype "bidirectional"))
      (node (ref "J7") (pin "15") (pinfunction "15_15") (pintype "passive"))
      (node (ref "R22") (pin "1") (pinfunction "1_1") (pintype "passive"))
    )
    (net (code "16") (name "I2C_SDA") (class "Default")
      (node (ref "IC5") (pin "23") (pinfunction "SDA_23") (pintype "input"))
      (node (ref "J100") (pin "3") (pinfunction "GPIO2/SDA1_3") (pintype "bidirectional"))
      (node (ref "J7") (pin "13") (pinfunction "13_13") (pintype "passive"))
      (node (ref "R23") (pin "1") (pinfunction "1_1") (pintype "passive"))
    )
    (net (code "17") (name "I2S_BCK") (class "Default")
      (node (ref "IC3") (pin "16") (pinfunction "BCLK_16") (pintype "bidirectional"))
      (node (ref "J100") (pin "12") (pinfunction "GPIO18_12") (pintype "bidirectional"))
    )
    (net (code "18") (name "I2S_DOUT") (class "Default")
      (node (ref "IC3") (pin "1") (pinfunction "DIN_1") (pintype "bidirectional"))
      (node (ref "J100") (pin "40") (pinfunction "GPIO21_40") (pintype "bidirectional"))
    )
    (net (code "19") (name "I2S_WS{slash}LRCLK") (class "Default")
      (node (ref "IC3") (pin "14") (pinfunction "LRCLK_14") (pintype "bidirectional"))
      (node (ref "J100") (pin "35") (pinfunction "GPIO19_35") (pintype "bidirectional"))
    )
    (net (code "20") (name "IN0") (class "Default")
      (node (ref "D4") (pin "3") (pinfunction "C1A2_3") (pintype "passive"))
      (node (ref "IC5") (pin "4") (pinfunction "P00_4") (pintype "bidirectional"))
      (node (ref "IC6") (pin "16") (pinfunction "C_16") (pintype "passive"))
      (node (ref "R37") (pin "1") (pinfunction "1_1") (pintype "passive"))
      (node (ref "R38") (pin "1") (pinfunction "1_1") (pintype "passive"))
    )
    (net (code "21") (name "IN0P") (class "Default")
      (node (ref "J5") (pin "1") (pinfunction "1_1") (pintype "bidirectional"))
      (node (ref "J7") (pin "16") (pinfunction "16_16") (pintype "passive"))
      (node (ref "R37") (pin "2") (pinfunction "2_2") (pintype "passive"))
    )
    (net (code "22") (name "IN1") (class "Default")
      (node (ref "D5") (pin "3") (pinfunction "C1A2_3") (pintype "passive"))
      (node (ref "IC5") (pin "5") (pinfunction "P01_5") (pintype "bidirectional"))
      (node (ref "IC6") (pin "14") (pinfunction "C_14") (pintype "passive"))
      (node (ref "R39") (pin "1") (pinfunction "1_1") (pintype "passive"))
      (node (ref "R40") (pin "1") (pinfunction "1_1") (pintype "passive"))
    )
    (net (code "23") (name "IN1P") (class "Default")
      (node (ref "J5") (pin "2") (pinfunction "2_2") (pintype "bidirectional"))
      (node (ref "J7") (pin "14") (pinfunction "14_14") (pintype "passive"))
      (node (ref "R40") (pin "2") (pinfunction "2_2") (pintype "passive"))
    )
    (net (code "24") (name "IN2") (class "Default")
      (node (ref "D6") (pin "3") (pinfunction "C1A2_3") (pintype "passive"))
      (node (ref "IC5") (pin "6") (pinfunction "P02_6") (pintype "bidirectional"))
      (node (ref "IC6") (pin "12") (pinfunction "C_12") (pintype "passive"))
      (node (ref "R35") (pin "1") (pinfunction "1_1") (pintype "passive"))
      (node (ref "R43") (pin "1") (pinfunction "1_1") (pintype "passive"))
    )
    (net (code "25") (name "IN2P") (class "Default")
      (node (ref "J7") (pin "12") (pinfunction "12_12") (pintype "passive"))
      (node (ref "J8") (pin "1") (pinfunction "1_1") (pintype "bidirectional"))
      (node (ref "R43") (pin "2") (pinfunction "2_2") (pintype "passive"))
    )
    (net (code "26") (name "IN3") (class "Default")
      (node (ref "D7") (pin "3") (pinfunction "C1A2_3") (pintype "passive"))
      (node (ref "IC5") (pin "7") (pinfunction "P03_7") (pintype "bidirectional"))
      (node (ref "IC6") (pin "10") (pinfunction "C_10") (pintype "passive"))
      (node (ref "R36") (pin "1") (pinfunction "1_1") (pintype "passive"))
      (node (ref "R46") (pin "1") (pinfunction "1_1") (pintype "passive"))
    )
    (net (code "27") (name "IN3P") (class "Default")
      (node (ref "J7") (pin "10") (pinfunction "10_10") (pintype "passive"))
      (node (ref "J8") (pin "2") (pinfunction "2_2") (pintype "bidirectional"))
      (node (ref "R46") (pin "2") (pinfunction "2_2") (pintype "passive"))
    )
    (net (code "28") (name "LCD_BACKLIGHT") (class "Default")
      (node (ref "J100") (pin "29") (pinfunction "GPIO5_29") (pintype "bidirectional"))
      (node (ref "SJ1") (pin "2") (pinfunction "2_2") (pintype "passive"))
    )
    (net (code "29") (name "LCD_CS") (class "Default")
      (node (ref "J100") (pin "24") (pinfunction "~{CE0}/GPIO8_24") (pintype "bidirectional"))
      (node (ref "SJ2") (pin "2") (pinfunction "2_2") (pintype "passive"))
    )
    (net (code "30") (name "LCD_D{slash}C") (class "Default")
      (node (ref "J100") (pin "18") (pinfunction "GEN5/GPIO24_18") (pintype "bidirectional"))
      (node (ref "SJ5") (pin "2") (pinfunction "2_2") (pintype "passive"))
    )
    (net (code "31") (name "LCD_MISO") (class "Default")
      (node (ref "J100") (pin "21") (pinfunction "GPIO9/MISO_21") (pintype "bidirectional"))
    )
    (net (code "32") (name "LCD_MOSI") (class "Default")
      (node (ref "J100") (pin "19") (pinfunction "GPIO10/MOSI_19") (pintype "bidirectional"))
      (node (ref "SJ4") (pin "2") (pinfunction "2_2") (pintype "passive"))
    )
    (net (code "33") (name "LCD_RESET") (class "Default")
      (node (ref "J100") (pin "16") (pinfunction "GEN4/GPIO23_16") (pintype "bidirectional"))
      (node (ref "SJ6") (pin "2") (pinfunction "2_2") (pintype "passive"))
    )
    (net (code "34") (name "LCD_SCK") (class "Default")
      (node (ref "J100") (pin "23") (pinfunction "GPIO11/SCLK_23") (pintype "bidirectional"))
      (node (ref "SJ3") (pin "2") (pinfunction "2_2") (pintype "passive"))
    )
    (net (code "35") (name "LED0") (class "Default")
      (node (ref "IC5") (pin "17") (pinfunction "P14_17") (pintype "bidirectional"))
      (node (ref "LED101") (pin "K") (pinfunction "C_K") (pintype "passive"))
    )
    (net (code "36") (name "LED1") (class "Default")
      (node (ref "IC5") (pin "18") (pinfunction "P15_18") (pintype "bidirectional"))
      (node (ref "LED100") (pin "K") (pinfunction "C_K") (pintype "passive"))
    )
    (net (code "37") (name "Net-(FB1-P$1)") (class "Default")
      (node (ref "FB1") (pin "1") (pinfunction "P$1_1") (pintype "passive"))
      (node (ref "IC3") (pin "10") (pinfunction "OUTN_10") (pintype "output"))
    )
    (net (code "38") (name "Net-(FB1-P$2)") (class "Default")
      (node (ref "C1") (pin "1") (pinfunction "1_1") (pintype "passive"))
      (node (ref "FB1") (pin "2") (pinfunction "P$2_2") (pintype "passive"))
      (node (ref "J1") (pin "1") (pinfunction "1_1") (pintype "passive"))
    )
    (net (code "39") (name "Net-(FB2-P$1)") (class "Default")
      (node (ref "FB2") (pin "1") (pinfunction "P$1_1") (pintype "passive"))
      (node (ref "IC3") (pin "9") (pinfunction "OUTP_9") (pintype "output"))
    )
    (net (code "40") (name "Net-(FB2-P$2)") (class "Default")
      (node (ref "C4") (pin "1") (pinfunction "1_1") (pintype "passive"))
      (node (ref "FB2") (pin "2") (pinfunction "P$2_2") (pintype "passive"))
      (node (ref "J1") (pin "2") (pinfunction "2_2") (pintype "passive"))
    )
    (net (code "41") (name "Net-(FB3-P$1)") (class "Default")
      (node (ref "C11") (pin "1") (pinfunction "1_1") (pintype "passive"))
      (node (ref "C12") (pin "1") (pinfunction "1_1") (pintype "passive"))
      (node (ref "FB3") (pin "1") (pinfunction "P$1_1") (pintype "passive"))
      (node (ref "FB4") (pin "1") (pinfunction "P$1_1") (pintype "passive"))
      (node (ref "J4") (pin "2") (pinfunction "2_2") (pintype "passive"))
    )
    (net (code "42") (name "Net-(IC1-PROG)") (class "Default")
      (node (ref "IC1") (pin "5") (pinfunction "PROG_5") (pintype "input"))
      (node (ref "R2") (pin "2") (pinfunction "2_2") (pintype "passive"))
    )
    (net (code "43") (name "Net-(IC2-D1)") (class "Default")
      (node (ref "IC2") (pin "3") (pinfunction "D1_3") (pintype "input"))
      (node (ref "R6") (pin "2") (pinfunction "2_2") (pintype "passive"))
    )
    (net (code "44") (name "Net-(IC2-ILIM)") (class "Default")
      (node (ref "IC2") (pin "4") (pinfunction "ILIM_4") (pintype "input"))
      (node (ref "R4") (pin "2") (pinfunction "2_2") (pintype "passive"))
    )
    (net (code "45") (name "Net-(IC3-GAIN)") (class "Default")
      (node (ref "IC3") (pin "2") (pinfunction "GAIN_2") (pintype "bidirectional"))
      (node (ref "R10") (pin "1") (pinfunction "1_1") (pintype "passive"))
      (node (ref "R11") (pin "1") (pinfunction "1_1") (pintype "passive"))
    )
    (net (code "46") (name "Net-(IC3-~{SD_MODE})") (class "Default")
      (node (ref "IC3") (pin "4") (pinfunction "~{SD_MODE}_4") (pintype "bidirectional"))
      (node (ref "R9") (pin "1") (pinfunction "1_1") (pintype "passive"))
    )
    (net (code "47") (name "Net-(IC4-EN)") (class "Default")
      (node (ref "IC4") (pin "3") (pinfunction "EN_3") (pintype "input"))
      (node (ref "R17") (pin "1") (pinfunction "1_1") (pintype "passive"))
    )
    (net (code "48") (name "Net-(IC5-A0)") (class "Default")
      (node (ref "IC5") (pin "21") (pinfunction "A0_21") (pintype "bidirectional"))
      (node (ref "R26") (pin "2") (pinfunction "2_2") (pintype "passive"))
    )
    (net (code "49") (name "Net-(IC5-A1)") (class "Default")
      (node (ref "IC5") (pin "2") (pinfunction "A1_2") (pintype "input"))
      (node (ref "R28") (pin "2") (pinfunction "2_2") (pintype "passive"))
    )
    (net (code "50") (name "Net-(IC5-P16)") (class "Default")
      (node (ref "IC5") (pin "19") (pinfunction "P16_19") (pintype "bidirectional"))
      (node (ref "R27") (pin "1") (pinfunction "1_1") (pintype "passive"))
    )
    (net (code "51") (name "Net-(IC5-P17)") (class "Default")
      (node (ref "IC5") (pin "20") (pinfunction "P17_20") (pintype "bidirectional"))
      (node (ref "R25") (pin "1") (pinfunction "1_1") (pintype "passive"))
    )
    (net (code "52") (name "Net-(IC6A-AC1)") (class "Default")
      (node (ref "IC6") (pin "1") (pinfunction "AC1_1") (pintype "passive"))
      (node (ref "R51") (pin "2") (pinfunction "2_2") (pintype "passive"))
    )
    (net (code "53") (name "Net-(IC6A-AC2)") (class "Default")
      (node (ref "IC6") (pin "2") (pinfunction "AC2_2") (pintype "passive"))
      (node (ref "R52") (pin "1") (pinfunction "1_1") (pintype "passive"))
    )
    (net (code "54") (name "Net-(IC6B-AC1)") (class "Default")
      (node (ref "IC6") (pin "3") (pinfunction "AC1_3") (pintype "passive"))
      (node (ref "R53") (pin "2") (pinfunction "2_2") (pintype "passive"))
    )
    (net (code "55") (name "Net-(IC6B-AC2)") (class "Default")
      (node (ref "IC6") (pin "4") (pinfunction "AC2_4") (pintype "passive"))
      (node (ref "R54") (pin "1") (pinfunction "1_1") (pintype "passive"))
    )
    (net (code "56") (name "Net-(IC6C-AC1)") (class "Default")
      (node (ref "IC6") (pin "5") (pinfunction "AC1_5") (pintype "passive"))
      (node (ref "R55") (pin "2") (pinfunction "2_2") (pintype "passive"))
    )
    (net (code "57") (name "Net-(IC6C-AC2)") (class "Default")
      (node (ref "IC6") (pin "6") (pinfunction "AC2_6") (pintype "passive"))
      (node (ref "R56") (pin "1") (pinfunction "1_1") (pintype "passive"))
    )
    (net (code "58") (name "Net-(IC6D-AC1)") (class "Default")
      (node (ref "IC6") (pin "7") (pinfunction "AC1_7") (pintype "passive"))
      (node (ref "R57") (pin "2") (pinfunction "2_2") (pintype "passive"))
    )
    (net (code "59") (name "Net-(IC6D-AC2)") (class "Default")
      (node (ref "IC6") (pin "8") (pinfunction "AC2_8") (pintype "passive"))
      (node (ref "R58") (pin "1") (pinfunction "1_1") (pintype "passive"))
    )
    (net (code "60") (name "Net-(IC7-ANODE)") (class "Default")
      (node (ref "IC7") (pin "1") (pinfunction "ANODE_1") (pintype "passive"))
      (node (ref "R47") (pin "1") (pinfunction "1_1") (pintype "passive"))
    )
    (net (code "61") (name "Net-(IC7-DC+)") (class "Default")
      (node (ref "IC7") (pin "4") (pinfunction "DC+_4") (pintype "passive"))
      (node (ref "J11") (pin "2") (pinfunction "1_2") (pintype "passive"))
    )
    (net (code "62") (name "Net-(IC7-DC-)") (class "Default")
      (node (ref "IC7") (pin "3") (pinfunction "DC-_3") (pintype "passive"))
      (node (ref "J11") (pin "1") (pinfunction "1_1") (pintype "passive"))
    )
    (net (code "63") (name "Net-(IC8-ANODE)") (class "Default")
      (node (ref "IC8") (pin "1") (pinfunction "ANODE_1") (pintype "passive"))
      (node (ref "R48") (pin "1") (pinfunction "1_1") (pintype "passive"))
    )
    (net (code "64") (name "Net-(IC8-DC+)") (class "Default")
      (node (ref "IC8") (pin "4") (pinfunction "DC+_4") (pintype "passive"))
      (node (ref "J11") (pin "4") (pinfunction "1_4") (pintype "passive"))
    )
    (net (code "65") (name "Net-(IC8-DC-)") (class "Default")
      (node (ref "IC8") (pin "3") (pinfunction "DC-_3") (pintype "passive"))
      (node (ref "J11") (pin "3") (pinfunction "1_3") (pintype "passive"))
    )
    (net (code "66") (name "Net-(IC9-ANODE)") (class "Default")
      (node (ref "IC9") (pin "1") (pinfunction "ANODE_1") (pintype "passive"))
      (node (ref "R49") (pin "1") (pinfunction "1_1") (pintype "passive"))
    )
    (net (code "67") (name "Net-(IC9-DC+)") (class "Default")
      (node (ref "IC9") (pin "4") (pinfunction "DC+_4") (pintype "passive"))
      (node (ref "J11") (pin "6") (pinfunction "1_6") (pintype "passive"))
    )
    (net (code "68") (name "Net-(IC9-DC-)") (class "Default")
      (node (ref "IC9") (pin "3") (pinfunction "DC-_3") (pintype "passive"))
      (node (ref "J11") (pin "5") (pinfunction "1_5") (pintype "passive"))
    )
    (net (code "69") (name "Net-(IC10-ANODE)") (class "Default")
      (node (ref "IC10") (pin "1") (pinfunction "ANODE_1") (pintype "passive"))
      (node (ref "R50") (pin "1") (pinfunction "1_1") (pintype "passive"))
    )
    (net (code "70") (name "Net-(IC10-DC+)") (class "Default")
      (node (ref "IC10") (pin "4") (pinfunction "DC+_4") (pintype "passive"))
      (node (ref "J11") (pin "8") (pinfunction "1_8") (pintype "passive"))
    )
    (net (code "71") (name "Net-(IC10-DC-)") (class "Default")
      (node (ref "IC10") (pin "3") (pinfunction "DC-_3") (pintype "passive"))
      (node (ref "J11") (pin "7") (pinfunction "1_7") (pintype "passive"))
    )
    (net (code "72") (name "Net-(J4-Pad4)") (class "Default")
      (node (ref "J4") (pin "4") (pinfunction "4_4") (pintype "passive"))
      (node (ref "R24") (pin "2") (pinfunction "2_2") (pintype "passive"))
    )
    (net (code "73") (name "Net-(J10-Pad1)") (class "Default")
      (node (ref "J10") (pin "1") (pinfunction "1_1") (pintype "passive"))
      (node (ref "R51") (pin "1") (pinfunction "1_1") (pintype "passive"))
    )
    (net (code "74") (name "Net-(J10B-1)") (class "Default")
      (node (ref "J10") (pin "2") (pinfunction "1_2") (pintype "passive"))
      (node (ref "R52") (pin "2") (pinfunction "2_2") (pintype "passive"))
    )
    (net (code "75") (name "Net-(J10C-1)") (class "Default")
      (node (ref "J10") (pin "3") (pinfunction "1_3") (pintype "passive"))
      (node (ref "R53") (pin "1") (pinfunction "1_1") (pintype "passive"))
    )
    (net (code "76") (name "Net-(J10D-1)") (class "Default")
      (node (ref "J10") (pin "4") (pinfunction "1_4") (pintype "passive"))
      (node (ref "R54") (pin "2") (pinfunction "2_2") (pintype "passive"))
    )
    (net (code "77") (name "Net-(J10E-1)") (class "Default")
      (node (ref "J10") (pin "5") (pinfunction "1_5") (pintype "passive"))
      (node (ref "R55") (pin "1") (pinfunction "1_1") (pintype "passive"))
    )
    (net (code "78") (name "Net-(J10F-1)") (class "Default")
      (node (ref "J10") (pin "6") (pinfunction "1_6") (pintype "passive"))
      (node (ref "R56") (pin "2") (pinfunction "2_2") (pintype "passive"))
    )
    (net (code "79") (name "Net-(J10G-1)") (class "Default")
      (node (ref "J10") (pin "7") (pinfunction "1_7") (pintype "passive"))
      (node (ref "R57") (pin "1") (pinfunction "1_1") (pintype "passive"))
    )
    (net (code "80") (name "Net-(J10H-1)") (class "Default")
      (node (ref "J10") (pin "8") (pinfunction "1_8") (pintype "passive"))
      (node (ref "R58") (pin "2") (pinfunction "2_2") (pintype "passive"))
    )
    (net (code "81") (name "Net-(J100-3V3-Pad1)") (class "Default")
      (node (ref "J100") (pin "1") (pinfunction "3V3_1") (pintype "power_in"))
      (node (ref "J100") (pin "17") (pinfunction "3V3_17") (pintype "power_in"))
      (node (ref "R16") (pin "1") (pinfunction "1_1") (pintype "passive"))
    )
    (net (code "82") (name "Net-(LCD100-A0)") (class "Default")
      (node (ref "LCD100") (pin "7") (pinfunction "A0_7") (pintype "bidirectional"))
      (node (ref "SJ5") (pin "1") (pinfunction "1_1") (pintype "passive"))
    )
    (net (code "83") (name "Net-(LCD100-LED+)") (class "Default")
      (node (ref "LCD100") (pin "15") (pinfunction "LED+_15") (pintype "bidirectional"))
      (node (ref "R14") (pin "2") (pinfunction "2_2") (pintype "passive"))
    )
    (net (code "84") (name "Net-(LCD100-RESET)") (class "Default")
      (node (ref "LCD100") (pin "6") (pinfunction "RESET_6") (pintype "bidirectional"))
      (node (ref "SJ6") (pin "1") (pinfunction "1_1") (pintype "passive"))
    )
    (net (code "85") (name "Net-(LCD100-TFT_CLK)") (class "Default")
      (node (ref "LCD100") (pin "9") (pinfunction "TFT_CLK_9") (pintype "bidirectional"))
      (node (ref "SJ3") (pin "1") (pinfunction "1_1") (pintype "passive"))
    )
    (net (code "86") (name "Net-(LCD100-TFT_CS)") (class "Default")
      (node (ref "LCD100") (pin "10") (pinfunction "TFT_CS_10") (pintype "bidirectional"))
      (node (ref "SJ2") (pin "1") (pinfunction "1_1") (pintype "passive"))
    )
    (net (code "87") (name "Net-(LCD100-TFT_DAT)") (class "Default")
      (node (ref "LCD100") (pin "8") (pinfunction "TFT_DAT_8") (pintype "bidirectional"))
      (node (ref "SJ4") (pin "1") (pinfunction "1_1") (pintype "passive"))
    )
    (net (code "88") (name "Net-(LED1-PadA)") (class "Default")
      (node (ref "LED1") (pin "A") (pinfunction "A_A") (pintype "passive"))
      (node (ref "R1") (pin "2") (pinfunction "2_2") (pintype "passive"))
    )
    (net (code "89") (name "Net-(LED2-PadA)") (class "Default")
      (node (ref "LED2") (pin "A") (pinfunction "A_A") (pintype "passive"))
      (node (ref "R3") (pin "2") (pinfunction "2_2") (pintype "passive"))
    )
    (net (code "90") (name "Net-(LED3-PadA)") (class "Default")
      (node (ref "LED3") (pin "A") (pinfunction "A_A") (pintype "passive"))
      (node (ref "R7") (pin "2") (pinfunction "2_2") (pintype "passive"))
    )
    (net (code "91") (name "Net-(LED4-PadA)") (class "Default")
      (node (ref "LED4") (pin "A") (pinfunction "A_A") (pintype "passive"))
      (node (ref "R5") (pin "2") (pinfunction "2_2") (pintype "passive"))
    )
    (net (code "92") (name "Net-(LED100-PadA)") (class "Default")
      (node (ref "LED100") (pin "A") (pinfunction "A_A") (pintype "passive"))
      (node (ref "R30") (pin "1") (pinfunction "1_1") (pintype "passive"))
    )
    (net (code "93") (name "Net-(LED101-PadA)") (class "Default")
      (node (ref "LED101") (pin "A") (pinfunction "A_A") (pintype "passive"))
      (node (ref "R29") (pin "1") (pinfunction "1_1") (pintype "passive"))
    )
    (net (code "94") (name "Net-(Q1-D)") (class "Default")
      (node (ref "Q1") (pin "3") (pinfunction "D_3") (pintype "passive"))
      (node (ref "R14") (pin "1") (pinfunction "1_1") (pintype "passive"))
    )
    (net (code "95") (name "Net-(Q1-G)") (class "Default")
      (node (ref "Q1") (pin "1") (pinfunction "G_1") (pintype "passive"))
      (node (ref "R15") (pin "2") (pinfunction "2_2") (pintype "passive"))
      (node (ref "SJ1") (pin "1") (pinfunction "1_1") (pintype "passive"))
    )
    (net (code "96") (name "OUT0") (class "Default")
      (node (ref "D3") (pin "3") (pinfunction "C1A2_3") (pintype "passive"))
      (node (ref "IC5") (pin "8") (pinfunction "P04_8") (pintype "bidirectional"))
      (node (ref "R45") (pin "1") (pinfunction "1_1") (pintype "passive"))
      (node (ref "R47") (pin "2") (pinfunction "2_2") (pintype "passive"))
    )
    (net (code "97") (name "OUT0P") (class "Default")
      (node (ref "J7") (pin "1") (pinfunction "1_1") (pintype "passive"))
      (node (ref "J9") (pin "1") (pinfunction "1_1") (pintype "bidirectional"))
      (node (ref "R45") (pin "2") (pinfunction "2_2") (pintype "passive"))
    )
    (net (code "98") (name "OUT1") (class "Default")
      (node (ref "D10") (pin "3") (pinfunction "C1A2_3") (pintype "passive"))
      (node (ref "IC5") (pin "9") (pinfunction "P05_9") (pintype "bidirectional"))
      (node (ref "R44") (pin "1") (pinfunction "1_1") (pintype "passive"))
      (node (ref "R48") (pin "2") (pinfunction "2_2") (pintype "passive"))
    )
    (net (code "99") (name "OUT1P") (class "Default")
      (node (ref "J7") (pin "3") (pinfunction "3_3") (pintype "passive"))
      (node (ref "J9") (pin "2") (pinfunction "2_2") (pintype "bidirectional"))
      (node (ref "R44") (pin "2") (pinfunction "2_2") (pintype "passive"))
    )
    (net (code "100") (name "OUT2") (class "Default")
      (node (ref "D8") (pin "3") (pinfunction "C1A2_3") (pintype "passive"))
      (node (ref "IC5") (pin "10") (pinfunction "P06_10") (pintype "bidirectional"))
      (node (ref "R42") (pin "1") (pinfunction "1_1") (pintype "passive"))
      (node (ref "R49") (pin "2") (pinfunction "2_2") (pintype "passive"))
    )
    (net (code "101") (name "OUT2P") (class "Default")
      (node (ref "J6") (pin "1") (pinfunction "1_1") (pintype "bidirectional"))
      (node (ref "J7") (pin "5") (pinfunction "5_5") (pintype "passive"))
      (node (ref "R42") (pin "2") (pinfunction "2_2") (pintype "passive"))
    )
    (net (code "102") (name "OUT3") (class "Default")
      (node (ref "D9") (pin "3") (pinfunction "C1A2_3") (pintype "passive"))
      (node (ref "IC5") (pin "11") (pinfunction "P07_11") (pintype "bidirectional"))
      (node (ref "R41") (pin "1") (pinfunction "1_1") (pintype "passive"))
      (node (ref "R50") (pin "2") (pinfunction "2_2") (pintype "passive"))
    )
    (net (code "103") (name "OUT3P") (class "Default")
      (node (ref "J6") (pin "2") (pinfunction "2_2") (pintype "bidirectional"))
      (node (ref "J7") (pin "7") (pinfunction "7_7") (pintype "passive"))
      (node (ref "R41") (pin "2") (pinfunction "2_2") (pintype "passive"))
    )
    (net (code "104") (name "RFID_RX") (class "Default")
      (node (ref "D2") (pin "3") (pinfunction "C1A2_3") (pintype "passive"))
      (node (ref "J100") (pin "8") (pinfunction "TXD0/GPIO14_8") (pintype "bidirectional"))
      (node (ref "J7") (pin "11") (pinfunction "11_11") (pintype "passive"))
      (node (ref "R24") (pin "1") (pinfunction "1_1") (pintype "passive"))
    )
    (net (code "105") (name "RFID_TX") (class "Default")
      (node (ref "D1") (pin "3") (pinfunction "C1A2_3") (pintype "passive"))
      (node (ref "J100") (pin "10") (pinfunction "RXD0/GPIO15_10") (pintype "bidirectional"))
      (node (ref "J7") (pin "9") (pinfunction "9_9") (pintype "passive"))
      (node (ref "R19") (pin "2") (pinfunction "2_2") (pintype "passive"))
      (node (ref "R21") (pin "1") (pinfunction "1_1") (pintype "passive"))
    )
    (net (code "106") (name "SHUTDOWN") (class "Default")
      (node (ref "IC2") (pin "2") (pinfunction "D0_2") (pintype "input"))
      (node (ref "J100") (pin "13") (pinfunction "GPIO27/GEN2_13") (pintype "bidirectional"))
      (node (ref "R8") (pin "2") (pinfunction "2_2") (pintype "passive"))
    )
    (net (code "107") (name "unconnected-(IC4-BP-Pad4)") (class "Default")
      (node (ref "IC4") (pin "4") (pinfunction "BP_4") (pintype "input"))
    )
    (net (code "108") (name "unconnected-(J100-GEN{slash}6GPIO25-Pad22)") (class "Default")
      (node (ref "J100") (pin "22") (pinfunction "GEN/6GPIO25_22") (pintype "bidirectional"))
    )
    (net (code "109") (name "unconnected-(J100-GPIO6-Pad31)") (class "Default")
      (node (ref "J100") (pin "31") (pinfunction "GPIO6_31") (pintype "bidirectional"))
    )
    (net (code "110") (name "unconnected-(J100-GPIO13-Pad33)") (class "Default")
      (node (ref "J100") (pin "33") (pinfunction "GPIO13_33") (pintype "bidirectional"))
    )
    (net (code "111") (name "unconnected-(J100-GPIO16-Pad36)") (class "Default")
      (node (ref "J100") (pin "36") (pinfunction "GPIO16_36") (pintype "bidirectional"))
    )
    (net (code "112") (name "unconnected-(J100-GPIO20-Pad38)") (class "Default")
      (node (ref "J100") (pin "38") (pinfunction "GPIO20_38") (pintype "bidirectional"))
    )
    (net (code "113") (name "unconnected-(J100-GPIO22{slash}GEN3-Pad15)") (class "Default")
      (node (ref "J100") (pin "15") (pinfunction "GPIO22/GEN3_15") (pintype "bidirectional"))
    )
    (net (code "114") (name "unconnected-(J100-ID_SC-Pad28)") (class "Default")
      (node (ref "J100") (pin "28") (pinfunction "ID_SC_28") (pintype "bidirectional"))
    )
    (net (code "115") (name "unconnected-(J100-ID_SD-Pad27)") (class "Default")
      (node (ref "J100") (pin "27") (pinfunction "ID_SD_27") (pintype "bidirectional"))
    )
    (net (code "116") (name "unconnected-(J100-~{CE}{slash}GPIO7-Pad26)") (class "Default")
      (node (ref "J100") (pin "26") (pinfunction "~{CE}/GPIO7_26") (pintype "bidirectional"))
    )
    (net (code "117") (name "unconnected-(LCD100-NC-Pad3)") (class "Default")
      (node (ref "LCD100") (pin "3") (pinfunction "NC_3") (pintype "bidirectional"))
    )
    (net (code "118") (name "unconnected-(LCD100-NC-Pad4)") (class "Default")
      (node (ref "LCD100") (pin "4") (pinfunction "NC_4") (pintype "bidirectional"))
    )
    (net (code "119") (name "unconnected-(LCD100-NC-Pad5)") (class "Default")
      (node (ref "LCD100") (pin "5") (pinfunction "NC_5") (pintype "bidirectional"))
    )
    (net (code "120") (name "unconnected-(LCD100-SD_CS-Pad14)") (class "Default")
      (node (ref "LCD100") (pin "14") (pinfunction "SD_CS_14") (pintype "bidirectional"))
    )
    (net (code "121") (name "unconnected-(LCD100-SD_MISO-Pad12)") (class "Default")
      (node (ref "LCD100") (pin "12") (pinfunction "SD_MISO_12") (pintype "bidirectional"))
    )
    (net (code "122") (name "unconnected-(LCD100-SD_MOSI-Pad13)") (class "Default")
      (node (ref "LCD100") (pin "13") (pinfunction "SD_MOSI_13") (pintype "bidirectional"))
    )
    (net (code "123") (name "unconnected-(LCD100-SD_SCK-Pad11)") (class "Default")
      (node (ref "LCD100") (pin "11") (pinfunction "SD_SCK_11") (pintype "bidirectional"))
    )
  )
)
